# Schematico_prova_3a_1.net
KiCad netlist of a schematic drawn in EAGLE
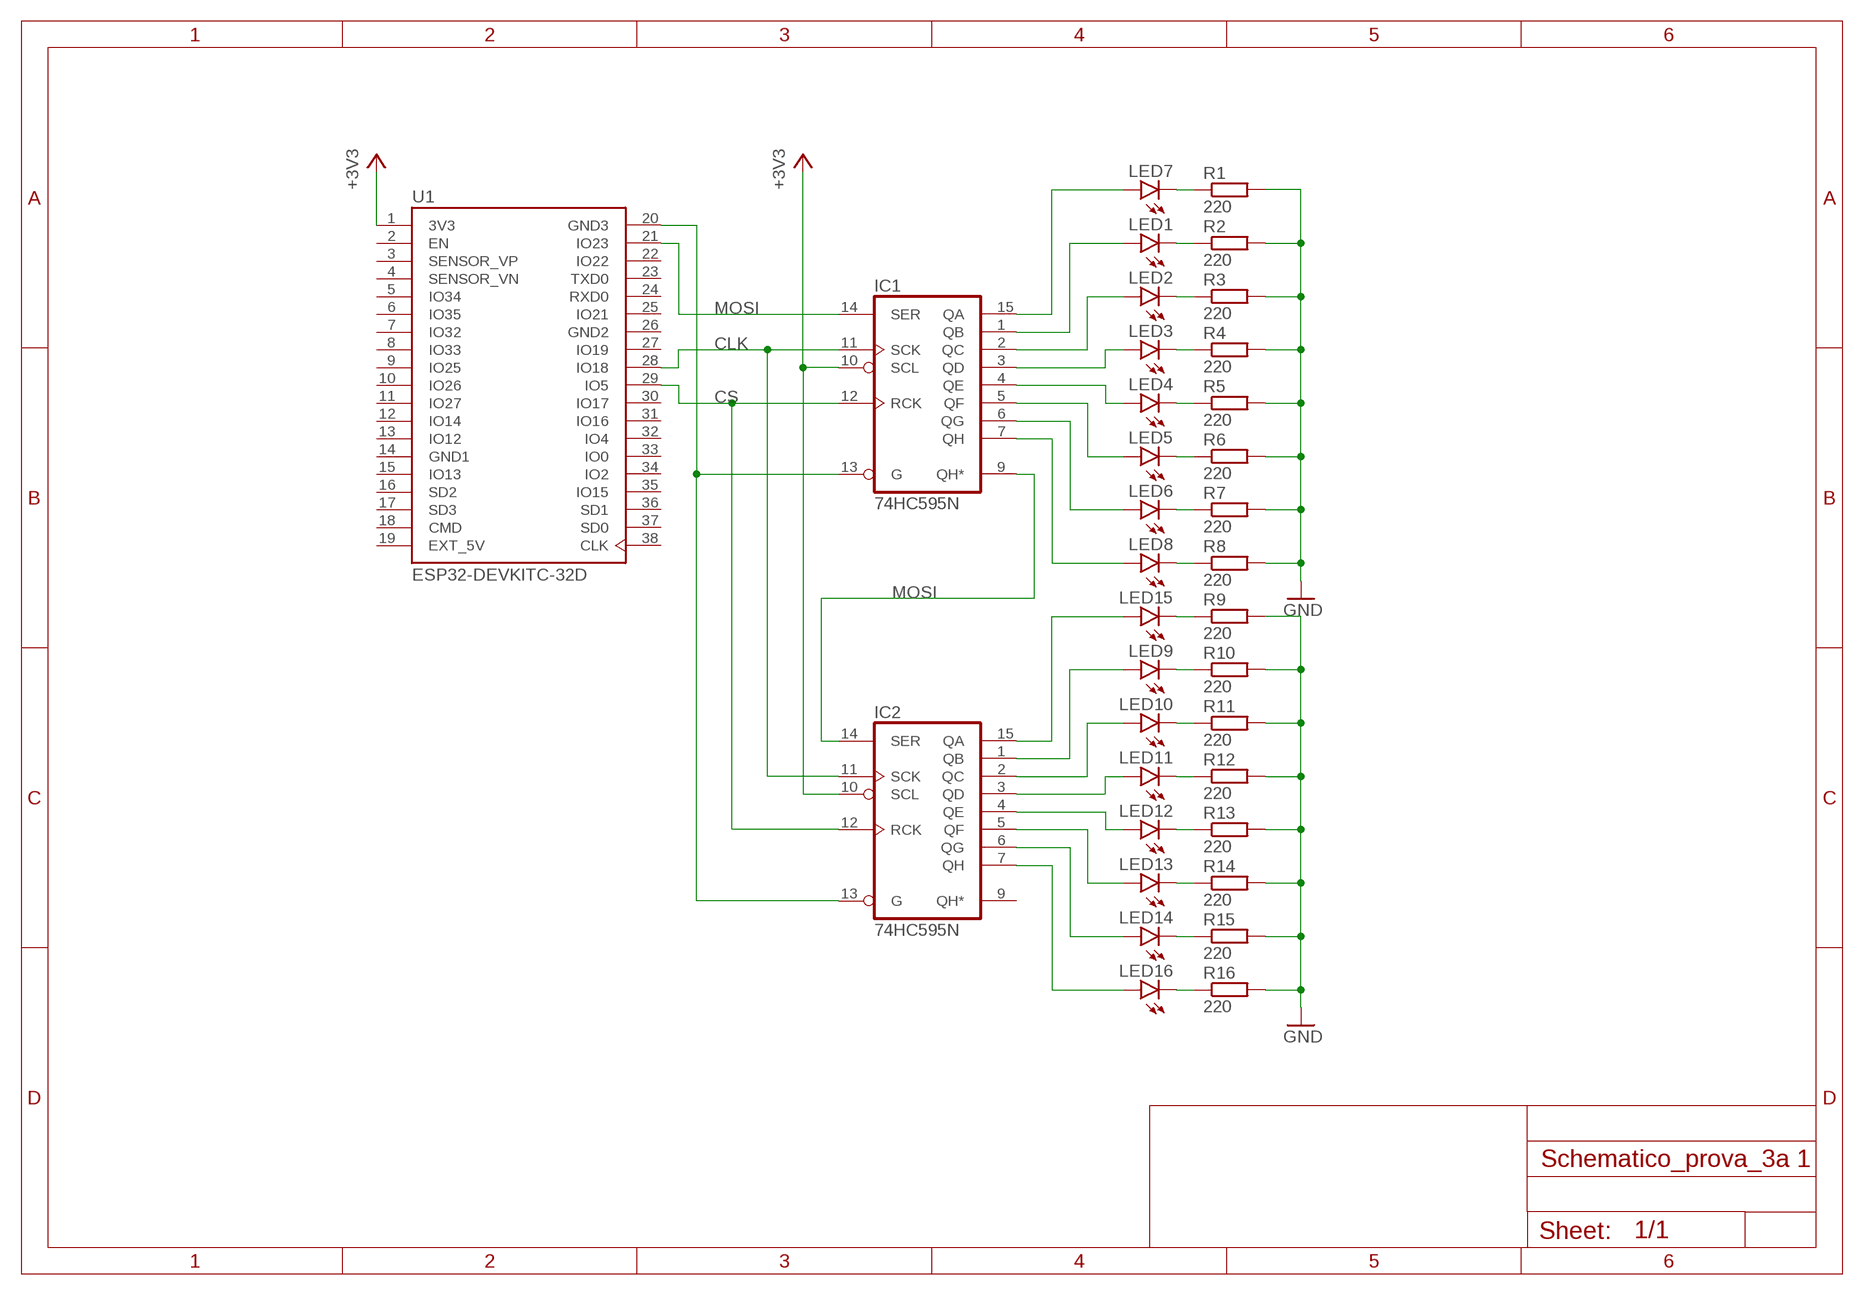
[diagram p0: schematic, sheet 1]

(export (version "E")
  (design (tool "Eeschema 10.0.6"))
  (components
    (comp (ref "IC1")
      (value "74HC595N")
      (footprint "eagle-import:DIL16")
      (libsource (lib "eagle-import") (part "74595NHC"))
    )
    (comp (ref "IC2")
      (value "74HC595N")
      (footprint "eagle-import:DIL16")
      (libsource (lib "eagle-import") (part "74595NHC"))
    )
    (comp (ref "LED1")
      (value "LED")
      (footprint "eagle-import:SMARTLED-TTW")
      (libsource (lib "eagle-import") (part "LED"))
    )
    (comp (ref "LED2")
      (value "LED")
      (footprint "eagle-import:SMARTLED-TTW")
      (libsource (lib "eagle-import") (part "LED"))
    )
    (comp (ref "LED3")
      (value "LED")
      (footprint "eagle-import:SMARTLED-TTW")
      (libsource (lib "eagle-import") (part "LED"))
    )
    (comp (ref "LED4")
      (value "LED")
      (footprint "eagle-import:SMARTLED-TTW")
      (libsource (lib "eagle-import") (part "LED"))
    )
    (comp (ref "LED5")
      (value "LED")
      (footprint "eagle-import:SMARTLED-TTW")
      (libsource (lib "eagle-import") (part "LED"))
    )
    (comp (ref "LED6")
      (value "LED")
      (footprint "eagle-import:SMARTLED-TTW")
      (libsource (lib "eagle-import") (part "LED"))
    )
    (comp (ref "LED7")
      (value "LED")
      (footprint "eagle-import:SMARTLED-TTW")
      (libsource (lib "eagle-import") (part "LED"))
    )
    (comp (ref "LED8")
      (value "LED")
      (footprint "eagle-import:SMARTLED-TTW")
      (libsource (lib "eagle-import") (part "LED"))
    )
    (comp (ref "LED9")
      (value "LED")
      (footprint "eagle-import:SMARTLED-TTW")
      (libsource (lib "eagle-import") (part "LED"))
    )
    (comp (ref "LED10")
      (value "LED")
      (footprint "eagle-import:SMARTLED-TTW")
      (libsource (lib "eagle-import") (part "LED"))
    )
    (comp (ref "LED11")
      (value "LED")
      (footprint "eagle-import:SMARTLED-TTW")
      (libsource (lib "eagle-import") (part "LED"))
    )
    (comp (ref "LED12")
      (value "LED")
      (footprint "eagle-import:SMARTLED-TTW")
      (libsource (lib "eagle-import") (part "LED"))
    )
    (comp (ref "LED13")
      (value "LED")
      (footprint "eagle-import:SMARTLED-TTW")
      (libsource (lib "eagle-import") (part "LED"))
    )
    (comp (ref "LED14")
      (value "LED")
      (footprint "eagle-import:SMARTLED-TTW")
      (libsource (lib "eagle-import") (part "LED"))
    )
    (comp (ref "LED15")
      (value "LED")
      (footprint "eagle-import:SMARTLED-TTW")
      (libsource (lib "eagle-import") (part "LED"))
    )
    (comp (ref "LED16")
      (value "LED")
      (footprint "eagle-import:SMARTLED-TTW")
      (libsource (lib "eagle-import") (part "LED"))
    )
    (comp (ref "R1")
      (value "220")
      (footprint "eagle-import:M1406")
      (libsource (lib "eagle-import") (part "R-EU_M1406"))
    )
    (comp (ref "R2")
      (value "220")
      (footprint "eagle-import:M1406")
      (libsource (lib "eagle-import") (part "R-EU_M1406"))
    )
    (comp (ref "R3")
      (value "220")
      (footprint "eagle-import:M1406")
      (libsource (lib "eagle-import") (part "R-EU_M1406"))
    )
    (comp (ref "R4")
      (value "220")
      (footprint "eagle-import:M1406")
      (libsource (lib "eagle-import") (part "R-EU_M1406"))
    )
    (comp (ref "R5")
      (value "220")
      (footprint "eagle-import:M1406")
      (libsource (lib "eagle-import") (part "R-EU_M1406"))
    )
    (comp (ref "R6")
      (value "220")
      (footprint "eagle-import:M1406")
      (libsource (lib "eagle-import") (part "R-EU_M1406"))
    )
    (comp (ref "R7")
      (value "220")
      (footprint "eagle-import:M1406")
      (libsource (lib "eagle-import") (part "R-EU_M1406"))
    )
    (comp (ref "R8")
      (value "220")
      (footprint "eagle-import:M1406")
      (libsource (lib "eagle-import") (part "R-EU_M1406"))
    )
    (comp (ref "R9")
      (value "220")
      (footprint "eagle-import:M1406")
      (libsource (lib "eagle-import") (part "R-EU_M1406"))
    )
    (comp (ref "R10")
      (value "220")
      (footprint "eagle-import:M1406")
      (libsource (lib "eagle-import") (part "R-EU_M1406"))
    )
    (comp (ref "R11")
      (value "220")
      (footprint "eagle-import:M1406")
      (libsource (lib "eagle-import") (part "R-EU_M1406"))
    )
    (comp (ref "R12")
      (value "220")
      (footprint "eagle-import:M1406")
      (libsource (lib "eagle-import") (part "R-EU_M1406"))
    )
    (comp (ref "R13")
      (value "220")
      (footprint "eagle-import:M1406")
      (libsource (lib "eagle-import") (part "R-EU_M1406"))
    )
    (comp (ref "R14")
      (value "220")
      (footprint "eagle-import:M1406")
      (libsource (lib "eagle-import") (part "R-EU_M1406"))
    )
    (comp (ref "R15")
      (value "220")
      (footprint "eagle-import:M1406")
      (libsource (lib "eagle-import") (part "R-EU_M1406"))
    )
    (comp (ref "R16")
      (value "220")
      (footprint "eagle-import:M1406")
      (libsource (lib "eagle-import") (part "R-EU_M1406"))
    )
    (comp (ref "U1")
      (value "ESP32-DEVKITC-32D")
      (footprint "eagle-import:MODULE_ESP32-DEVKITC-32D")
      (fields (field (name "MF") "Espressif Systems"))
      (libsource (lib "eagle-import") (part "ESP32-DEVKITC-32D"))
    )
  )
  (nets
    (net (code "1") (name "+3V3") (class "Default")
      (node (ref "IC1") (pin "10") (pinfunction "SCL_10") (pintype "input"))
      (node (ref "IC2") (pin "10") (pinfunction "SCL_10") (pintype "input"))
      (node (ref "U1") (pin "1") (pinfunction "3V3_1") (pintype "power_in"))
    )
    (net (code "2") (name "/CLK") (class "Default")
      (node (ref "IC1") (pin "11") (pinfunction "SCK_11") (pintype "input"))
      (node (ref "IC2") (pin "11") (pinfunction "SCK_11") (pintype "input"))
      (node (ref "U1") (pin "28") (pinfunction "IO18_28") (pintype "bidirectional"))
    )
    (net (code "3") (name "/CS") (class "Default")
      (node (ref "IC1") (pin "12") (pinfunction "RCK_12") (pintype "input"))
      (node (ref "IC2") (pin "12") (pinfunction "RCK_12") (pintype "input"))
      (node (ref "U1") (pin "29") (pinfunction "IO5_29") (pintype "bidirectional"))
    )
    (net (code "4") (name "/EXT_5V") (class "Default")
      (node (ref "U1") (pin "19") (pinfunction "EXT_5V_19") (pintype "power_in"))
    )
    (net (code "5") (name "/GND1") (class "Default")
      (node (ref "U1") (pin "14") (pinfunction "GND1_14") (pintype "power_in"))
    )
    (net (code "6") (name "/GND2") (class "Default")
      (node (ref "U1") (pin "26") (pinfunction "GND2_26") (pintype "power_in"))
    )
    (net (code "7") (name "/MOSI") (class "Default")
      (node (ref "IC1") (pin "14") (pinfunction "SER_14") (pintype "input"))
      (node (ref "IC1") (pin "9") (pinfunction "QH*_9") (pintype "tri_state"))
      (node (ref "IC2") (pin "14") (pinfunction "SER_14") (pintype "input"))
      (node (ref "U1") (pin "21") (pinfunction "IO23_21") (pintype "bidirectional"))
    )
    (net (code "8") (name "GND") (class "Default")
      (node (ref "R1") (pin "2") (pinfunction "2_2") (pintype "passive"))
      (node (ref "R10") (pin "2") (pinfunction "2_2") (pintype "passive"))
      (node (ref "R11") (pin "2") (pinfunction "2_2") (pintype "passive"))
      (node (ref "R12") (pin "2") (pinfunction "2_2") (pintype "passive"))
      (node (ref "R13") (pin "2") (pinfunction "2_2") (pintype "passive"))
      (node (ref "R14") (pin "2") (pinfunction "2_2") (pintype "passive"))
      (node (ref "R15") (pin "2") (pinfunction "2_2") (pintype "passive"))
      (node (ref "R16") (pin "2") (pinfunction "2_2") (pintype "passive"))
      (node (ref "R2") (pin "2") (pinfunction "2_2") (pintype "passive"))
      (node (ref "R3") (pin "2") (pinfunction "2_2") (pintype "passive"))
      (node (ref "R4") (pin "2") (pinfunction "2_2") (pintype "passive"))
      (node (ref "R5") (pin "2") (pinfunction "2_2") (pintype "passive"))
      (node (ref "R6") (pin "2") (pinfunction "2_2") (pintype "passive"))
      (node (ref "R7") (pin "2") (pinfunction "2_2") (pintype "passive"))
      (node (ref "R8") (pin "2") (pinfunction "2_2") (pintype "passive"))
      (node (ref "R9") (pin "2") (pinfunction "2_2") (pintype "passive"))
    )
    (net (code "9") (name "Net-(IC1A-G)") (class "Default")
      (node (ref "IC1") (pin "13") (pinfunction "G_13") (pintype "input"))
      (node (ref "IC2") (pin "13") (pinfunction "G_13") (pintype "input"))
      (node (ref "U1") (pin "20") (pinfunction "GND3_20") (pintype "power_in"))
    )
    (net (code "10") (name "Net-(IC1A-QA)") (class "Default")
      (node (ref "IC1") (pin "15") (pinfunction "QA_15") (pintype "tri_state"))
      (node (ref "LED7") (pin "A@1") (pinfunction "A_A@1") (pintype "passive"))
    )
    (net (code "11") (name "Net-(IC1A-QB)") (class "Default")
      (node (ref "IC1") (pin "1") (pinfunction "QB_1") (pintype "tri_state"))
      (node (ref "LED1") (pin "A@1") (pinfunction "A_A@1") (pintype "passive"))
    )
    (net (code "12") (name "Net-(IC1A-QC)") (class "Default")
      (node (ref "IC1") (pin "2") (pinfunction "QC_2") (pintype "tri_state"))
      (node (ref "LED2") (pin "A@1") (pinfunction "A_A@1") (pintype "passive"))
    )
    (net (code "13") (name "Net-(IC1A-QD)") (class "Default")
      (node (ref "IC1") (pin "3") (pinfunction "QD_3") (pintype "tri_state"))
      (node (ref "LED3") (pin "A@1") (pinfunction "A_A@1") (pintype "passive"))
    )
    (net (code "14") (name "Net-(IC1A-QE)") (class "Default")
      (node (ref "IC1") (pin "4") (pinfunction "QE_4") (pintype "tri_state"))
      (node (ref "LED4") (pin "A@1") (pinfunction "A_A@1") (pintype "passive"))
    )
    (net (code "15") (name "Net-(IC1A-QF)") (class "Default")
      (node (ref "IC1") (pin "5") (pinfunction "QF_5") (pintype "tri_state"))
      (node (ref "LED5") (pin "A@1") (pinfunction "A_A@1") (pintype "passive"))
    )
    (net (code "16") (name "Net-(IC1A-QG)") (class "Default")
      (node (ref "IC1") (pin "6") (pinfunction "QG_6") (pintype "tri_state"))
      (node (ref "LED6") (pin "A@1") (pinfunction "A_A@1") (pintype "passive"))
    )
    (net (code "17") (name "Net-(IC1A-QH)") (class "Default")
      (node (ref "IC1") (pin "7") (pinfunction "QH_7") (pintype "tri_state"))
      (node (ref "LED8") (pin "A@1") (pinfunction "A_A@1") (pintype "passive"))
    )
    (net (code "18") (name "Net-(IC2A-QA)") (class "Default")
      (node (ref "IC2") (pin "15") (pinfunction "QA_15") (pintype "tri_state"))
      (node (ref "LED15") (pin "A@1") (pinfunction "A_A@1") (pintype "passive"))
    )
    (net (code "19") (name "Net-(IC2A-QB)") (class "Default")
      (node (ref "IC2") (pin "1") (pinfunction "QB_1") (pintype "tri_state"))
      (node (ref "LED9") (pin "A@1") (pinfunction "A_A@1") (pintype "passive"))
    )
    (net (code "20") (name "Net-(IC2A-QC)") (class "Default")
      (node (ref "IC2") (pin "2") (pinfunction "QC_2") (pintype "tri_state"))
      (node (ref "LED10") (pin "A@1") (pinfunction "A_A@1") (pintype "passive"))
    )
    (net (code "21") (name "Net-(IC2A-QD)") (class "Default")
      (node (ref "IC2") (pin "3") (pinfunction "QD_3") (pintype "tri_state"))
      (node (ref "LED11") (pin "A@1") (pinfunction "A_A@1") (pintype "passive"))
    )
    (net (code "22") (name "Net-(IC2A-QE)") (class "Default")
      (node (ref "IC2") (pin "4") (pinfunction "QE_4") (pintype "tri_state"))
      (node (ref "LED12") (pin "A@1") (pinfunction "A_A@1") (pintype "passive"))
    )
    (net (code "23") (name "Net-(IC2A-QF)") (class "Default")
      (node (ref "IC2") (pin "5") (pinfunction "QF_5") (pintype "tri_state"))
      (node (ref "LED13") (pin "A@1") (pinfunction "A_A@1") (pintype "passive"))
    )
    (net (code "24") (name "Net-(IC2A-QG)") (class "Default")
      (node (ref "IC2") (pin "6") (pinfunction "QG_6") (pintype "tri_state"))
      (node (ref "LED14") (pin "A@1") (pinfunction "A_A@1") (pintype "passive"))
    )
    (net (code "25") (name "Net-(IC2A-QH)") (class "Default")
      (node (ref "IC2") (pin "7") (pinfunction "QH_7") (pintype "tri_state"))
      (node (ref "LED16") (pin "A@1") (pinfunction "A_A@1") (pintype "passive"))
    )
    (net (code "26") (name "Net-(LED1-C)") (class "Default")
      (node (ref "LED1") (pin "C@1") (pinfunction "C_C@1") (pintype "passive"))
      (node (ref "R2") (pin "1") (pinfunction "1_1") (pintype "passive"))
    )
    (net (code "27") (name "Net-(LED2-C)") (class "Default")
      (node (ref "LED2") (pin "C@1") (pinfunction "C_C@1") (pintype "passive"))
      (node (ref "R3") (pin "1") (pinfunction "1_1") (pintype "passive"))
    )
    (net (code "28") (name "Net-(LED3-C)") (class "Default")
      (node (ref "LED3") (pin "C@1") (pinfunction "C_C@1") (pintype "passive"))
      (node (ref "R4") (pin "1") (pinfunction "1_1") (pintype "passive"))
    )
    (net (code "29") (name "Net-(LED4-C)") (class "Default")
      (node (ref "LED4") (pin "C@1") (pinfunction "C_C@1") (pintype "passive"))
      (node (ref "R5") (pin "1") (pinfunction "1_1") (pintype "passive"))
    )
    (net (code "30") (name "Net-(LED5-C)") (class "Default")
      (node (ref "LED5") (pin "C@1") (pinfunction "C_C@1") (pintype "passive"))
      (node (ref "R6") (pin "1") (pinfunction "1_1") (pintype "passive"))
    )
    (net (code "31") (name "Net-(LED6-C)") (class "Default")
      (node (ref "LED6") (pin "C@1") (pinfunction "C_C@1") (pintype "passive"))
      (node (ref "R7") (pin "1") (pinfunction "1_1") (pintype "passive"))
    )
    (net (code "32") (name "Net-(LED7-C)") (class "Default")
      (node (ref "LED7") (pin "C@1") (pinfunction "C_C@1") (pintype "passive"))
      (node (ref "R1") (pin "1") (pinfunction "1_1") (pintype "passive"))
    )
    (net (code "33") (name "Net-(LED8-C)") (class "Default")
      (node (ref "LED8") (pin "C@1") (pinfunction "C_C@1") (pintype "passive"))
      (node (ref "R8") (pin "1") (pinfunction "1_1") (pintype "passive"))
    )
    (net (code "34") (name "Net-(LED9-C)") (class "Default")
      (node (ref "LED9") (pin "C@1") (pinfunction "C_C@1") (pintype "passive"))
      (node (ref "R10") (pin "1") (pinfunction "1_1") (pintype "passive"))
    )
    (net (code "35") (name "Net-(LED10-C)") (class "Default")
      (node (ref "LED10") (pin "C@1") (pinfunction "C_C@1") (pintype "passive"))
      (node (ref "R11") (pin "1") (pinfunction "1_1") (pintype "passive"))
    )
    (net (code "36") (name "Net-(LED11-C)") (class "Default")
      (node (ref "LED11") (pin "C@1") (pinfunction "C_C@1") (pintype "passive"))
      (node (ref "R12") (pin "1") (pinfunction "1_1") (pintype "passive"))
    )
    (net (code "37") (name "Net-(LED12-C)") (class "Default")
      (node (ref "LED12") (pin "C@1") (pinfunction "C_C@1") (pintype "passive"))
      (node (ref "R13") (pin "1") (pinfunction "1_1") (pintype "passive"))
    )
    (net (code "38") (name "Net-(LED13-C)") (class "Default")
      (node (ref "LED13") (pin "C@1") (pinfunction "C_C@1") (pintype "passive"))
      (node (ref "R14") (pin "1") (pinfunction "1_1") (pintype "passive"))
    )
    (net (code "39") (name "Net-(LED14-C)") (class "Default")
      (node (ref "LED14") (pin "C@1") (pinfunction "C_C@1") (pintype "passive"))
      (node (ref "R15") (pin "1") (pinfunction "1_1") (pintype "passive"))
    )
    (net (code "40") (name "Net-(LED15-C)") (class "Default")
      (node (ref "LED15") (pin "C@1") (pinfunction "C_C@1") (pintype "passive"))
      (node (ref "R9") (pin "1") (pinfunction "1_1") (pintype "passive"))
    )
    (net (code "41") (name "Net-(LED16-C)") (class "Default")
      (node (ref "LED16") (pin "C@1") (pinfunction "C_C@1") (pintype "passive"))
      (node (ref "R16") (pin "1") (pinfunction "1_1") (pintype "passive"))
    )
    (net (code "42") (name "unconnected-(IC2A-QH*-Pad9)") (class "Default")
      (node (ref "IC2") (pin "9") (pinfunction "QH*_9") (pintype "tri_state"))
    )
    (net (code "43") (name "unconnected-(U1-CLK-Pad38)") (class "Default")
      (node (ref "U1") (pin "38") (pinfunction "CLK_38") (pintype "input"))
    )
    (net (code "44") (name "unconnected-(U1-CMD-Pad18)") (class "Default")
      (node (ref "U1") (pin "18") (pinfunction "CMD_18") (pintype "bidirectional"))
    )
    (net (code "45") (name "unconnected-(U1-EN-Pad2)") (class "Default")
      (node (ref "U1") (pin "2") (pinfunction "EN_2") (pintype "input"))
    )
    (net (code "46") (name "unconnected-(U1-IO0-Pad33)") (class "Default")
      (node (ref "U1") (pin "33") (pinfunction "IO0_33") (pintype "bidirectional"))
    )
    (net (code "47") (name "unconnected-(U1-IO2-Pad34)") (class "Default")
      (node (ref "U1") (pin "34") (pinfunction "IO2_34") (pintype "bidirectional"))
    )
    (net (code "48") (name "unconnected-(U1-IO4-Pad32)") (class "Default")
      (node (ref "U1") (pin "32") (pinfunction "IO4_32") (pintype "bidirectional"))
    )
    (net (code "49") (name "unconnected-(U1-IO12-Pad13)") (class "Default")
      (node (ref "U1") (pin "13") (pinfunction "IO12_13") (pintype "bidirectional"))
    )
    (net (code "50") (name "unconnected-(U1-IO13-Pad15)") (class "Default")
      (node (ref "U1") (pin "15") (pinfunction "IO13_15") (pintype "bidirectional"))
    )
    (net (code "51") (name "unconnected-(U1-IO14-Pad12)") (class "Default")
      (node (ref "U1") (pin "12") (pinfunction "IO14_12") (pintype "bidirectional"))
    )
    (net (code "52") (name "unconnected-(U1-IO15-Pad35)") (class "Default")
      (node (ref "U1") (pin "35") (pinfunction "IO15_35") (pintype "bidirectional"))
    )
    (net (code "53") (name "unconnected-(U1-IO16-Pad31)") (class "Default")
      (node (ref "U1") (pin "31") (pinfunction "IO16_31") (pintype "bidirectional"))
    )
    (net (code "54") (name "unconnected-(U1-IO17-Pad30)") (class "Default")
      (node (ref "U1") (pin "30") (pinfunction "IO17_30") (pintype "bidirectional"))
    )
    (net (code "55") (name "unconnected-(U1-IO19-Pad27)") (class "Default")
      (node (ref "U1") (pin "27") (pinfunction "IO19_27") (pintype "bidirectional"))
    )
    (net (code "56") (name "unconnected-(U1-IO21-Pad25)") (class "Default")
      (node (ref "U1") (pin "25") (pinfunction "IO21_25") (pintype "bidirectional"))
    )
    (net (code "57") (name "unconnected-(U1-IO22-Pad22)") (class "Default")
      (node (ref "U1") (pin "22") (pinfunction "IO22_22") (pintype "bidirectional"))
    )
    (net (code "58") (name "unconnected-(U1-IO25-Pad9)") (class "Default")
      (node (ref "U1") (pin "9") (pinfunction "IO25_9") (pintype "bidirectional"))
    )
    (net (code "59") (name "unconnected-(U1-IO26-Pad10)") (class "Default")
      (node (ref "U1") (pin "10") (pinfunction "IO26_10") (pintype "bidirectional"))
    )
    (net (code "60") (name "unconnected-(U1-IO27-Pad11)") (class "Default")
      (node (ref "U1") (pin "11") (pinfunction "IO27_11") (pintype "bidirectional"))
    )
    (net (code "61") (name "unconnected-(U1-IO32-Pad7)") (class "Default")
      (node (ref "U1") (pin "7") (pinfunction "IO32_7") (pintype "bidirectional"))
    )
    (net (code "62") (name "unconnected-(U1-IO33-Pad8)") (class "Default")
      (node (ref "U1") (pin "8") (pinfunction "IO33_8") (pintype "bidirectional"))
    )
    (net (code "63") (name "unconnected-(U1-IO34-Pad5)") (class "Default")
      (node (ref "U1") (pin "5") (pinfunction "IO34_5") (pintype "bidirectional"))
    )
    (net (code "64") (name "unconnected-(U1-IO35-Pad6)") (class "Default")
      (node (ref "U1") (pin "6") (pinfunction "IO35_6") (pintype "bidirectional"))
    )
    (net (code "65") (name "unconnected-(U1-RXD0-Pad24)") (class "Default")
      (node (ref "U1") (pin "24") (pinfunction "RXD0_24") (pintype "input"))
    )
    (net (code "66") (name "unconnected-(U1-SD0-Pad37)") (class "Default")
      (node (ref "U1") (pin "37") (pinfunction "SD0_37") (pintype "bidirectional"))
    )
    (net (code "67") (name "unconnected-(U1-SD1-Pad36)") (class "Default")
      (node (ref "U1") (pin "36") (pinfunction "SD1_36") (pintype "bidirectional"))
    )
    (net (code "68") (name "unconnected-(U1-SD2-Pad16)") (class "Default")
      (node (ref "U1") (pin "16") (pinfunction "SD2_16") (pintype "bidirectional"))
    )
    (net (code "69") (name "unconnected-(U1-SD3-Pad17)") (class "Default")
      (node (ref "U1") (pin "17") (pinfunction "SD3_17") (pintype "bidirectional"))
    )
    (net (code "70") (name "unconnected-(U1-SENSOR_VN-Pad4)") (class "Default")
      (node (ref "U1") (pin "4") (pinfunction "SENSOR_VN_4") (pintype "input"))
    )
    (net (code "71") (name "unconnected-(U1-SENSOR_VP-Pad3)") (class "Default")
      (node (ref "U1") (pin "3") (pinfunction "SENSOR_VP_3") (pintype "input"))
    )
    (net (code "72") (name "unconnected-(U1-TXD0-Pad23)") (class "Default")
      (node (ref "U1") (pin "23") (pinfunction "TXD0_23") (pintype "output"))
    )
  )
)
